# STM32.net
KiCad netlist of a schematic drawn in Altium Designer
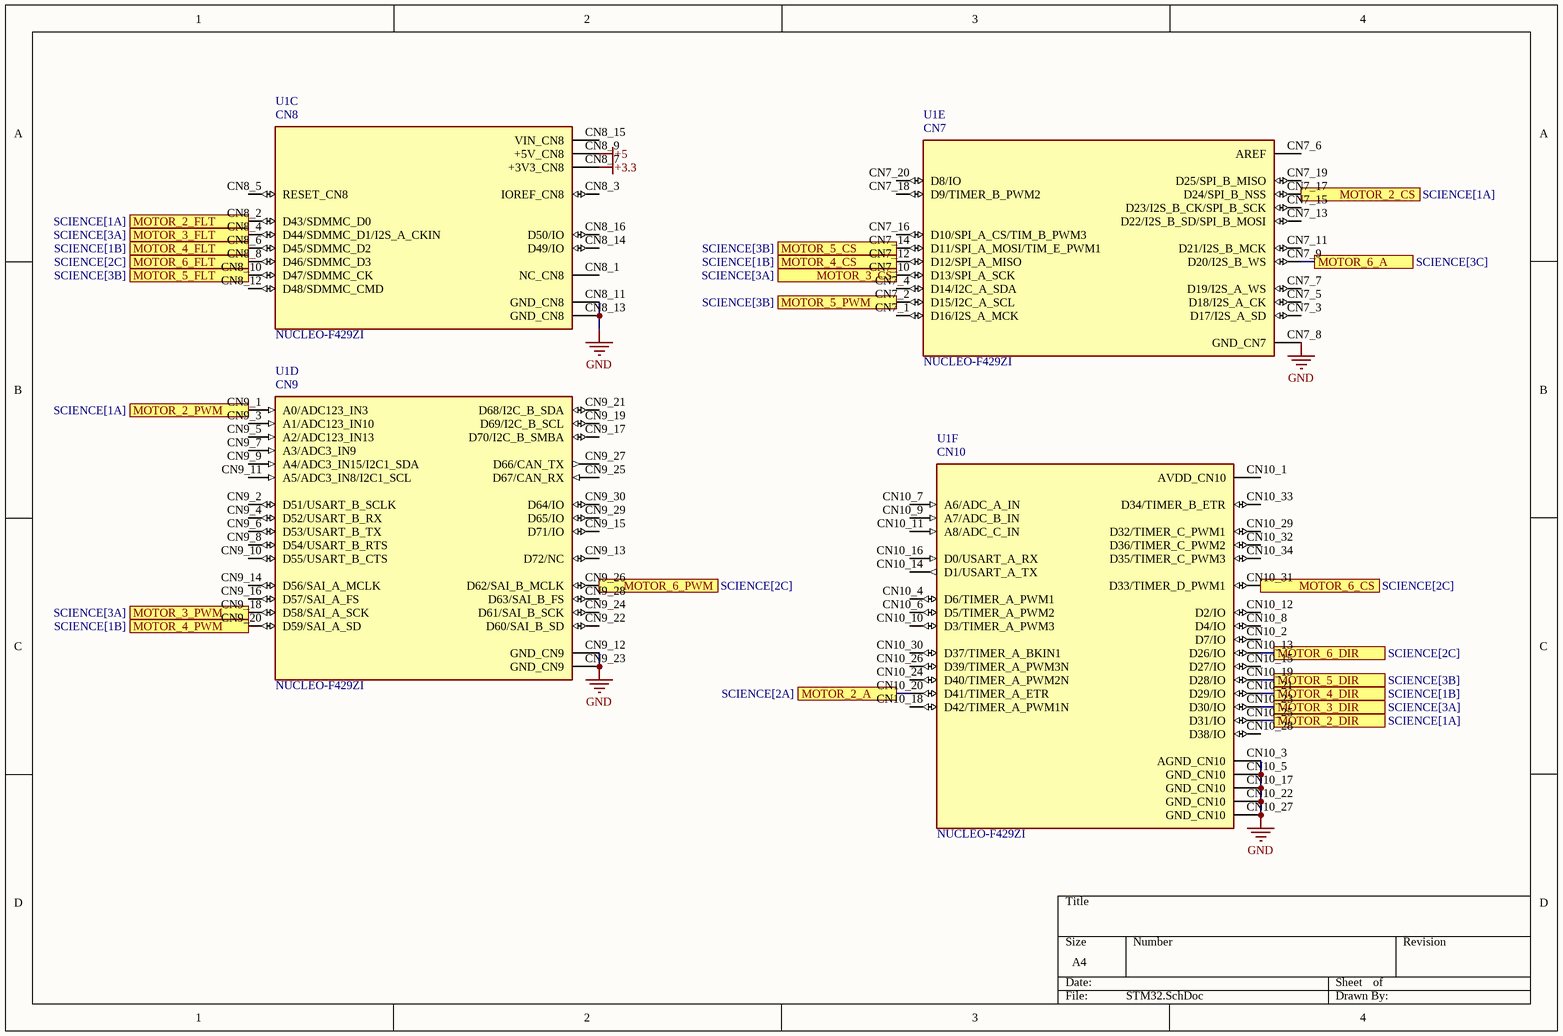
[diagram p0: STM32.SchDoc]

(export (version "E")
  (design (tool "Eeschema 10.0.6"))
  (components
    (comp (ref "U1")
      (value "NUCLEO-F429ZI")
      (footprint "MODULE_NUCLEO-F429ZI")
      (fields (field (name "MF") "STMicroelectronics"))
      (libsource (lib "NUCLEO-F429ZI") (part "NUCLEO-F429ZI"))
    )
  )
  (nets
    (net (code "1") (name "+3.3") (class "Default")
      (node (ref "U1") (pin "CN8_7") (pinfunction "+3V3_CN8_CN8_7") (pintype "power_in"))
    )
    (net (code "2") (name "+5") (class "Default")
      (node (ref "U1") (pin "CN8_9") (pinfunction "+5V_CN8_CN8_9") (pintype "power_in"))
    )
    (net (code "3") (name "/MOTOR_2_A") (class "Default")
      (node (ref "U1") (pin "CN10_20") (pinfunction "D41/TIMER_A_ETR_CN10_20") (pintype "bidirectional"))
    )
    (net (code "4") (name "/MOTOR_2_CS") (class "Default")
      (node (ref "U1") (pin "CN7_17") (pinfunction "D24/SPI_B_NSS_CN7_17") (pintype "bidirectional"))
    )
    (net (code "5") (name "/MOTOR_2_DIR") (class "Default")
      (node (ref "U1") (pin "CN10_25") (pinfunction "D31/IO_CN10_25") (pintype "bidirectional"))
    )
    (net (code "6") (name "/MOTOR_2_FLT") (class "Default")
      (node (ref "U1") (pin "CN8_2") (pinfunction "D43/SDMMC_D0_CN8_2") (pintype "bidirectional"))
    )
    (net (code "7") (name "/MOTOR_2_PWM") (class "Default")
      (node (ref "U1") (pin "CN9_1") (pinfunction "A0/ADC123_IN3_CN9_1") (pintype "input"))
    )
    (net (code "8") (name "/MOTOR_3_CS") (class "Default")
      (node (ref "U1") (pin "CN7_10") (pinfunction "D13/SPI_A_SCK_CN7_10") (pintype "bidirectional"))
    )
    (net (code "9") (name "/MOTOR_3_DIR") (class "Default")
      (node (ref "U1") (pin "CN10_23") (pinfunction "D30/IO_CN10_23") (pintype "bidirectional"))
    )
    (net (code "10") (name "/MOTOR_3_FLT") (class "Default")
      (node (ref "U1") (pin "CN8_4") (pinfunction "D44/SDMMC_D1/I2S_A_CKIN_CN8_4") (pintype "bidirectional"))
    )
    (net (code "11") (name "/MOTOR_3_PWM") (class "Default")
      (node (ref "U1") (pin "CN9_18") (pinfunction "D58/SAI_A_SCK_CN9_18") (pintype "bidirectional"))
    )
    (net (code "12") (name "/MOTOR_4_CS") (class "Default")
      (node (ref "U1") (pin "CN7_12") (pinfunction "D12/SPI_A_MISO_CN7_12") (pintype "bidirectional"))
    )
    (net (code "13") (name "/MOTOR_4_DIR") (class "Default")
      (node (ref "U1") (pin "CN10_21") (pinfunction "D29/IO_CN10_21") (pintype "bidirectional"))
    )
    (net (code "14") (name "/MOTOR_4_FLT") (class "Default")
      (node (ref "U1") (pin "CN8_6") (pinfunction "D45/SDMMC_D2_CN8_6") (pintype "bidirectional"))
    )
    (net (code "15") (name "/MOTOR_4_PWM") (class "Default")
      (node (ref "U1") (pin "CN9_20") (pinfunction "D59/SAI_A_SD_CN9_20") (pintype "bidirectional"))
    )
    (net (code "16") (name "/MOTOR_5_CS") (class "Default")
      (node (ref "U1") (pin "CN7_14") (pinfunction "D11/SPI_A_MOSI/TIM_E_PWM1_CN7_14") (pintype "bidirectional"))
    )
    (net (code "17") (name "/MOTOR_5_DIR") (class "Default")
      (node (ref "U1") (pin "CN10_19") (pinfunction "D28/IO_CN10_19") (pintype "bidirectional"))
    )
    (net (code "18") (name "/MOTOR_5_FLT") (class "Default")
      (node (ref "U1") (pin "CN8_10") (pinfunction "D47/SDMMC_CK_CN8_10") (pintype "bidirectional"))
    )
    (net (code "19") (name "/MOTOR_5_PWM") (class "Default")
      (node (ref "U1") (pin "CN7_2") (pinfunction "D15/I2C_A_SCL_CN7_2") (pintype "bidirectional"))
    )
    (net (code "20") (name "/MOTOR_6_A") (class "Default")
      (node (ref "U1") (pin "CN7_9") (pinfunction "D20/I2S_B_WS_CN7_9") (pintype "bidirectional"))
    )
    (net (code "21") (name "/MOTOR_6_CS") (class "Default")
      (node (ref "U1") (pin "CN10_31") (pinfunction "D33/TIMER_D_PWM1_CN10_31") (pintype "bidirectional"))
    )
    (net (code "22") (name "/MOTOR_6_DIR") (class "Default")
      (node (ref "U1") (pin "CN10_13") (pinfunction "D26/IO_CN10_13") (pintype "bidirectional"))
    )
    (net (code "23") (name "/MOTOR_6_FLT") (class "Default")
      (node (ref "U1") (pin "CN8_8") (pinfunction "D46/SDMMC_D3_CN8_8") (pintype "bidirectional"))
    )
    (net (code "24") (name "/MOTOR_6_PWM") (class "Default")
      (node (ref "U1") (pin "CN9_26") (pinfunction "D62/SAI_B_MCLK_CN9_26") (pintype "bidirectional"))
    )
    (net (code "25") (name "GND") (class "Default")
      (node (ref "U1") (pin "CN10_17") (pinfunction "GND_CN10_CN10_17") (pintype "power_in"))
      (node (ref "U1") (pin "CN10_22") (pinfunction "GND_CN10_CN10_22") (pintype "power_in"))
      (node (ref "U1") (pin "CN10_27") (pinfunction "GND_CN10_CN10_27") (pintype "power_in"))
      (node (ref "U1") (pin "CN10_3") (pinfunction "AGND_CN10_CN10_3") (pintype "power_in"))
      (node (ref "U1") (pin "CN10_5") (pinfunction "GND_CN10_CN10_5") (pintype "power_in"))
      (node (ref "U1") (pin "CN7_8") (pinfunction "GND_CN7_CN7_8") (pintype "power_in"))
      (node (ref "U1") (pin "CN8_11") (pinfunction "GND_CN8_CN8_11") (pintype "power_in"))
      (node (ref "U1") (pin "CN8_13") (pinfunction "GND_CN8_CN8_13") (pintype "power_in"))
      (node (ref "U1") (pin "CN9_12") (pinfunction "GND_CN9_CN9_12") (pintype "power_in"))
      (node (ref "U1") (pin "CN9_23") (pinfunction "GND_CN9_CN9_23") (pintype "power_in"))
    )
    (net (code "26") (name "unconnected-(U1C-D48{slash}SDMMC_CMD-PadCN8_12)") (class "Default")
      (node (ref "U1") (pin "CN8_12") (pinfunction "D48/SDMMC_CMD_CN8_12") (pintype "bidirectional"))
    )
    (net (code "27") (name "unconnected-(U1C-D49{slash}IO-PadCN8_14)") (class "Default")
      (node (ref "U1") (pin "CN8_14") (pinfunction "D49/IO_CN8_14") (pintype "bidirectional"))
    )
    (net (code "28") (name "unconnected-(U1C-D50{slash}IO-PadCN8_16)") (class "Default")
      (node (ref "U1") (pin "CN8_16") (pinfunction "D50/IO_CN8_16") (pintype "bidirectional"))
    )
    (net (code "29") (name "unconnected-(U1C-IOREF_CN8-PadCN8_3)") (class "Default")
      (node (ref "U1") (pin "CN8_3") (pinfunction "IOREF_CN8_CN8_3") (pintype "bidirectional"))
    )
    (net (code "30") (name "unconnected-(U1C-NC_CN8-PadCN8_1)") (class "Default")
      (node (ref "U1") (pin "CN8_1") (pinfunction "NC_CN8_CN8_1") (pintype "passive"))
    )
    (net (code "31") (name "unconnected-(U1C-RESET_CN8-PadCN8_5)") (class "Default")
      (node (ref "U1") (pin "CN8_5") (pinfunction "RESET_CN8_CN8_5") (pintype "bidirectional"))
    )
    (net (code "32") (name "unconnected-(U1C-VIN_CN8-PadCN8_15)") (class "Default")
      (node (ref "U1") (pin "CN8_15") (pinfunction "VIN_CN8_CN8_15") (pintype "power_in"))
    )
    (net (code "33") (name "unconnected-(U1D-A1{slash}ADC123_IN10-PadCN9_3)") (class "Default")
      (node (ref "U1") (pin "CN9_3") (pinfunction "A1/ADC123_IN10_CN9_3") (pintype "input"))
    )
    (net (code "34") (name "unconnected-(U1D-A2{slash}ADC123_IN13-PadCN9_5)") (class "Default")
      (node (ref "U1") (pin "CN9_5") (pinfunction "A2/ADC123_IN13_CN9_5") (pintype "input"))
    )
    (net (code "35") (name "unconnected-(U1D-A3{slash}ADC3_IN9-PadCN9_7)") (class "Default")
      (node (ref "U1") (pin "CN9_7") (pinfunction "A3/ADC3_IN9_CN9_7") (pintype "input"))
    )
    (net (code "36") (name "unconnected-(U1D-A4{slash}ADC3_IN15{slash}I2C1_SDA-PadCN9_9)") (class "Default")
      (node (ref "U1") (pin "CN9_9") (pinfunction "A4/ADC3_IN15/I2C1_SDA_CN9_9") (pintype "input"))
    )
    (net (code "37") (name "unconnected-(U1D-A5{slash}ADC3_IN8{slash}I2C1_SCL-PadCN9_11)") (class "Default")
      (node (ref "U1") (pin "CN9_11") (pinfunction "A5/ADC3_IN8/I2C1_SCL_CN9_11") (pintype "input"))
    )
    (net (code "38") (name "unconnected-(U1D-D51{slash}USART_B_SCLK-PadCN9_2)") (class "Default")
      (node (ref "U1") (pin "CN9_2") (pinfunction "D51/USART_B_SCLK_CN9_2") (pintype "bidirectional"))
    )
    (net (code "39") (name "unconnected-(U1D-D52{slash}USART_B_RX-PadCN9_4)") (class "Default")
      (node (ref "U1") (pin "CN9_4") (pinfunction "D52/USART_B_RX_CN9_4") (pintype "bidirectional"))
    )
    (net (code "40") (name "unconnected-(U1D-D53{slash}USART_B_TX-PadCN9_6)") (class "Default")
      (node (ref "U1") (pin "CN9_6") (pinfunction "D53/USART_B_TX_CN9_6") (pintype "bidirectional"))
    )
    (net (code "41") (name "unconnected-(U1D-D54{slash}USART_B_RTS-PadCN9_8)") (class "Default")
      (node (ref "U1") (pin "CN9_8") (pinfunction "D54/USART_B_RTS_CN9_8") (pintype "bidirectional"))
    )
    (net (code "42") (name "unconnected-(U1D-D55{slash}USART_B_CTS-PadCN9_10)") (class "Default")
      (node (ref "U1") (pin "CN9_10") (pinfunction "D55/USART_B_CTS_CN9_10") (pintype "bidirectional"))
    )
    (net (code "43") (name "unconnected-(U1D-D56{slash}SAI_A_MCLK-PadCN9_14)") (class "Default")
      (node (ref "U1") (pin "CN9_14") (pinfunction "D56/SAI_A_MCLK_CN9_14") (pintype "bidirectional"))
    )
    (net (code "44") (name "unconnected-(U1D-D57{slash}SAI_A_FS-PadCN9_16)") (class "Default")
      (node (ref "U1") (pin "CN9_16") (pinfunction "D57/SAI_A_FS_CN9_16") (pintype "bidirectional"))
    )
    (net (code "45") (name "unconnected-(U1D-D60{slash}SAI_B_SD-PadCN9_22)") (class "Default")
      (node (ref "U1") (pin "CN9_22") (pinfunction "D60/SAI_B_SD_CN9_22") (pintype "bidirectional"))
    )
    (net (code "46") (name "unconnected-(U1D-D61{slash}SAI_B_SCK-PadCN9_24)") (class "Default")
      (node (ref "U1") (pin "CN9_24") (pinfunction "D61/SAI_B_SCK_CN9_24") (pintype "bidirectional"))
    )
    (net (code "47") (name "unconnected-(U1D-D63{slash}SAI_B_FS-PadCN9_28)") (class "Default")
      (node (ref "U1") (pin "CN9_28") (pinfunction "D63/SAI_B_FS_CN9_28") (pintype "bidirectional"))
    )
    (net (code "48") (name "unconnected-(U1D-D64{slash}IO-PadCN9_30)") (class "Default")
      (node (ref "U1") (pin "CN9_30") (pinfunction "D64/IO_CN9_30") (pintype "bidirectional"))
    )
    (net (code "49") (name "unconnected-(U1D-D65{slash}IO-PadCN9_29)") (class "Default")
      (node (ref "U1") (pin "CN9_29") (pinfunction "D65/IO_CN9_29") (pintype "bidirectional"))
    )
    (net (code "50") (name "unconnected-(U1D-D66{slash}CAN_TX-PadCN9_27)") (class "Default")
      (node (ref "U1") (pin "CN9_27") (pinfunction "D66/CAN_TX_CN9_27") (pintype "output"))
    )
    (net (code "51") (name "unconnected-(U1D-D67{slash}CAN_RX-PadCN9_25)") (class "Default")
      (node (ref "U1") (pin "CN9_25") (pinfunction "D67/CAN_RX_CN9_25") (pintype "input"))
    )
    (net (code "52") (name "unconnected-(U1D-D68{slash}I2C_B_SDA-PadCN9_21)") (class "Default")
      (node (ref "U1") (pin "CN9_21") (pinfunction "D68/I2C_B_SDA_CN9_21") (pintype "bidirectional"))
    )
    (net (code "53") (name "unconnected-(U1D-D69{slash}I2C_B_SCL-PadCN9_19)") (class "Default")
      (node (ref "U1") (pin "CN9_19") (pinfunction "D69/I2C_B_SCL_CN9_19") (pintype "bidirectional"))
    )
    (net (code "54") (name "unconnected-(U1D-D70{slash}I2C_B_SMBA-PadCN9_17)") (class "Default")
      (node (ref "U1") (pin "CN9_17") (pinfunction "D70/I2C_B_SMBA_CN9_17") (pintype "bidirectional"))
    )
    (net (code "55") (name "unconnected-(U1D-D71{slash}IO-PadCN9_15)") (class "Default")
      (node (ref "U1") (pin "CN9_15") (pinfunction "D71/IO_CN9_15") (pintype "bidirectional"))
    )
    (net (code "56") (name "unconnected-(U1D-D72{slash}NC-PadCN9_13)") (class "Default")
      (node (ref "U1") (pin "CN9_13") (pinfunction "D72/NC_CN9_13") (pintype "bidirectional"))
    )
    (net (code "57") (name "unconnected-(U1E-AREF-PadCN7_6)") (class "Default")
      (node (ref "U1") (pin "CN7_6") (pinfunction "AREF_CN7_6") (pintype "power_in"))
    )
    (net (code "58") (name "unconnected-(U1E-D8{slash}IO-PadCN7_20)") (class "Default")
      (node (ref "U1") (pin "CN7_20") (pinfunction "D8/IO_CN7_20") (pintype "bidirectional"))
    )
    (net (code "59") (name "unconnected-(U1E-D9{slash}TIMER_B_PWM2-PadCN7_18)") (class "Default")
      (node (ref "U1") (pin "CN7_18") (pinfunction "D9/TIMER_B_PWM2_CN7_18") (pintype "bidirectional"))
    )
    (net (code "60") (name "unconnected-(U1E-D10{slash}SPI_A_CS{slash}TIM_B_PWM3-PadCN7_16)") (class "Default")
      (node (ref "U1") (pin "CN7_16") (pinfunction "D10/SPI_A_CS/TIM_B_PWM3_CN7_16") (pintype "bidirectional"))
    )
    (net (code "61") (name "unconnected-(U1E-D14{slash}I2C_A_SDA-PadCN7_4)") (class "Default")
      (node (ref "U1") (pin "CN7_4") (pinfunction "D14/I2C_A_SDA_CN7_4") (pintype "bidirectional"))
    )
    (net (code "62") (name "unconnected-(U1E-D16{slash}I2S_A_MCK-PadCN7_1)") (class "Default")
      (node (ref "U1") (pin "CN7_1") (pinfunction "D16/I2S_A_MCK_CN7_1") (pintype "bidirectional"))
    )
    (net (code "63") (name "unconnected-(U1E-D17{slash}I2S_A_SD-PadCN7_3)") (class "Default")
      (node (ref "U1") (pin "CN7_3") (pinfunction "D17/I2S_A_SD_CN7_3") (pintype "bidirectional"))
    )
    (net (code "64") (name "unconnected-(U1E-D18{slash}I2S_A_CK-PadCN7_5)") (class "Default")
      (node (ref "U1") (pin "CN7_5") (pinfunction "D18/I2S_A_CK_CN7_5") (pintype "bidirectional"))
    )
    (net (code "65") (name "unconnected-(U1E-D19{slash}I2S_A_WS-PadCN7_7)") (class "Default")
      (node (ref "U1") (pin "CN7_7") (pinfunction "D19/I2S_A_WS_CN7_7") (pintype "bidirectional"))
    )
    (net (code "66") (name "unconnected-(U1E-D21{slash}I2S_B_MCK-PadCN7_11)") (class "Default")
      (node (ref "U1") (pin "CN7_11") (pinfunction "D21/I2S_B_MCK_CN7_11") (pintype "bidirectional"))
    )
    (net (code "67") (name "unconnected-(U1E-D22{slash}I2S_B_SD{slash}SPI_B_MOSI-PadCN7_13)") (class "Default")
      (node (ref "U1") (pin "CN7_13") (pinfunction "D22/I2S_B_SD/SPI_B_MOSI_CN7_13") (pintype "bidirectional"))
    )
    (net (code "68") (name "unconnected-(U1E-D23{slash}I2S_B_CK{slash}SPI_B_SCK-PadCN7_15)") (class "Default")
      (node (ref "U1") (pin "CN7_15") (pinfunction "D23/I2S_B_CK/SPI_B_SCK_CN7_15") (pintype "bidirectional"))
    )
    (net (code "69") (name "unconnected-(U1E-D25{slash}SPI_B_MISO-PadCN7_19)") (class "Default")
      (node (ref "U1") (pin "CN7_19") (pinfunction "D25/SPI_B_MISO_CN7_19") (pintype "bidirectional"))
    )
    (net (code "70") (name "unconnected-(U1F-A6{slash}ADC_A_IN-PadCN10_7)") (class "Default")
      (node (ref "U1") (pin "CN10_7") (pinfunction "A6/ADC_A_IN_CN10_7") (pintype "input"))
    )
    (net (code "71") (name "unconnected-(U1F-A7{slash}ADC_B_IN-PadCN10_9)") (class "Default")
      (node (ref "U1") (pin "CN10_9") (pinfunction "A7/ADC_B_IN_CN10_9") (pintype "input"))
    )
    (net (code "72") (name "unconnected-(U1F-A8{slash}ADC_C_IN-PadCN10_11)") (class "Default")
      (node (ref "U1") (pin "CN10_11") (pinfunction "A8/ADC_C_IN_CN10_11") (pintype "input"))
    )
    (net (code "73") (name "unconnected-(U1F-AVDD_CN10-PadCN10_1)") (class "Default")
      (node (ref "U1") (pin "CN10_1") (pinfunction "AVDD_CN10_CN10_1") (pintype "power_in"))
    )
    (net (code "74") (name "unconnected-(U1F-D0{slash}USART_A_RX-PadCN10_16)") (class "Default")
      (node (ref "U1") (pin "CN10_16") (pinfunction "D0/USART_A_RX_CN10_16") (pintype "input"))
    )
    (net (code "75") (name "unconnected-(U1F-D1{slash}USART_A_TX-PadCN10_14)") (class "Default")
      (node (ref "U1") (pin "CN10_14") (pinfunction "D1/USART_A_TX_CN10_14") (pintype "output"))
    )
    (net (code "76") (name "unconnected-(U1F-D2{slash}IO-PadCN10_12)") (class "Default")
      (node (ref "U1") (pin "CN10_12") (pinfunction "D2/IO_CN10_12") (pintype "bidirectional"))
    )
    (net (code "77") (name "unconnected-(U1F-D3{slash}TIMER_A_PWM3-PadCN10_10)") (class "Default")
      (node (ref "U1") (pin "CN10_10") (pinfunction "D3/TIMER_A_PWM3_CN10_10") (pintype "bidirectional"))
    )
    (net (code "78") (name "unconnected-(U1F-D4{slash}IO-PadCN10_8)") (class "Default")
      (node (ref "U1") (pin "CN10_8") (pinfunction "D4/IO_CN10_8") (pintype "bidirectional"))
    )
    (net (code "79") (name "unconnected-(U1F-D5{slash}TIMER_A_PWM2-PadCN10_6)") (class "Default")
      (node (ref "U1") (pin "CN10_6") (pinfunction "D5/TIMER_A_PWM2_CN10_6") (pintype "bidirectional"))
    )
    (net (code "80") (name "unconnected-(U1F-D6{slash}TIMER_A_PWM1-PadCN10_4)") (class "Default")
      (node (ref "U1") (pin "CN10_4") (pinfunction "D6/TIMER_A_PWM1_CN10_4") (pintype "bidirectional"))
    )
    (net (code "81") (name "unconnected-(U1F-D7{slash}IO-PadCN10_2)") (class "Default")
      (node (ref "U1") (pin "CN10_2") (pinfunction "D7/IO_CN10_2") (pintype "bidirectional"))
    )
    (net (code "82") (name "unconnected-(U1F-D27{slash}IO-PadCN10_15)") (class "Default")
      (node (ref "U1") (pin "CN10_15") (pinfunction "D27/IO_CN10_15") (pintype "bidirectional"))
    )
    (net (code "83") (name "unconnected-(U1F-D32{slash}TIMER_C_PWM1-PadCN10_29)") (class "Default")
      (node (ref "U1") (pin "CN10_29") (pinfunction "D32/TIMER_C_PWM1_CN10_29") (pintype "bidirectional"))
    )
    (net (code "84") (name "unconnected-(U1F-D34{slash}TIMER_B_ETR-PadCN10_33)") (class "Default")
      (node (ref "U1") (pin "CN10_33") (pinfunction "D34/TIMER_B_ETR_CN10_33") (pintype "bidirectional"))
    )
    (net (code "85") (name "unconnected-(U1F-D35{slash}TIMER_C_PWM3-PadCN10_34)") (class "Default")
      (node (ref "U1") (pin "CN10_34") (pinfunction "D35/TIMER_C_PWM3_CN10_34") (pintype "bidirectional"))
    )
    (net (code "86") (name "unconnected-(U1F-D36{slash}TIMER_C_PWM2-PadCN10_32)") (class "Default")
      (node (ref "U1") (pin "CN10_32") (pinfunction "D36/TIMER_C_PWM2_CN10_32") (pintype "bidirectional"))
    )
    (net (code "87") (name "unconnected-(U1F-D37{slash}TIMER_A_BKIN1-PadCN10_30)") (class "Default")
      (node (ref "U1") (pin "CN10_30") (pinfunction "D37/TIMER_A_BKIN1_CN10_30") (pintype "bidirectional"))
    )
    (net (code "88") (name "unconnected-(U1F-D38{slash}IO-PadCN10_28)") (class "Default")
      (node (ref "U1") (pin "CN10_28") (pinfunction "D38/IO_CN10_28") (pintype "bidirectional"))
    )
    (net (code "89") (name "unconnected-(U1F-D39{slash}TIMER_A_PWM3N-PadCN10_26)") (class "Default")
      (node (ref "U1") (pin "CN10_26") (pinfunction "D39/TIMER_A_PWM3N_CN10_26") (pintype "bidirectional"))
    )
    (net (code "90") (name "unconnected-(U1F-D40{slash}TIMER_A_PWM2N-PadCN10_24)") (class "Default")
      (node (ref "U1") (pin "CN10_24") (pinfunction "D40/TIMER_A_PWM2N_CN10_24") (pintype "bidirectional"))
    )
    (net (code "91") (name "unconnected-(U1F-D42{slash}TIMER_A_PWM1N-PadCN10_18)") (class "Default")
      (node (ref "U1") (pin "CN10_18") (pinfunction "D42/TIMER_A_PWM1N_CN10_18") (pintype "bidirectional"))
    )
  )
)
